# ServerHardware.net
KiCad netlist of a schematic drawn in EAGLE
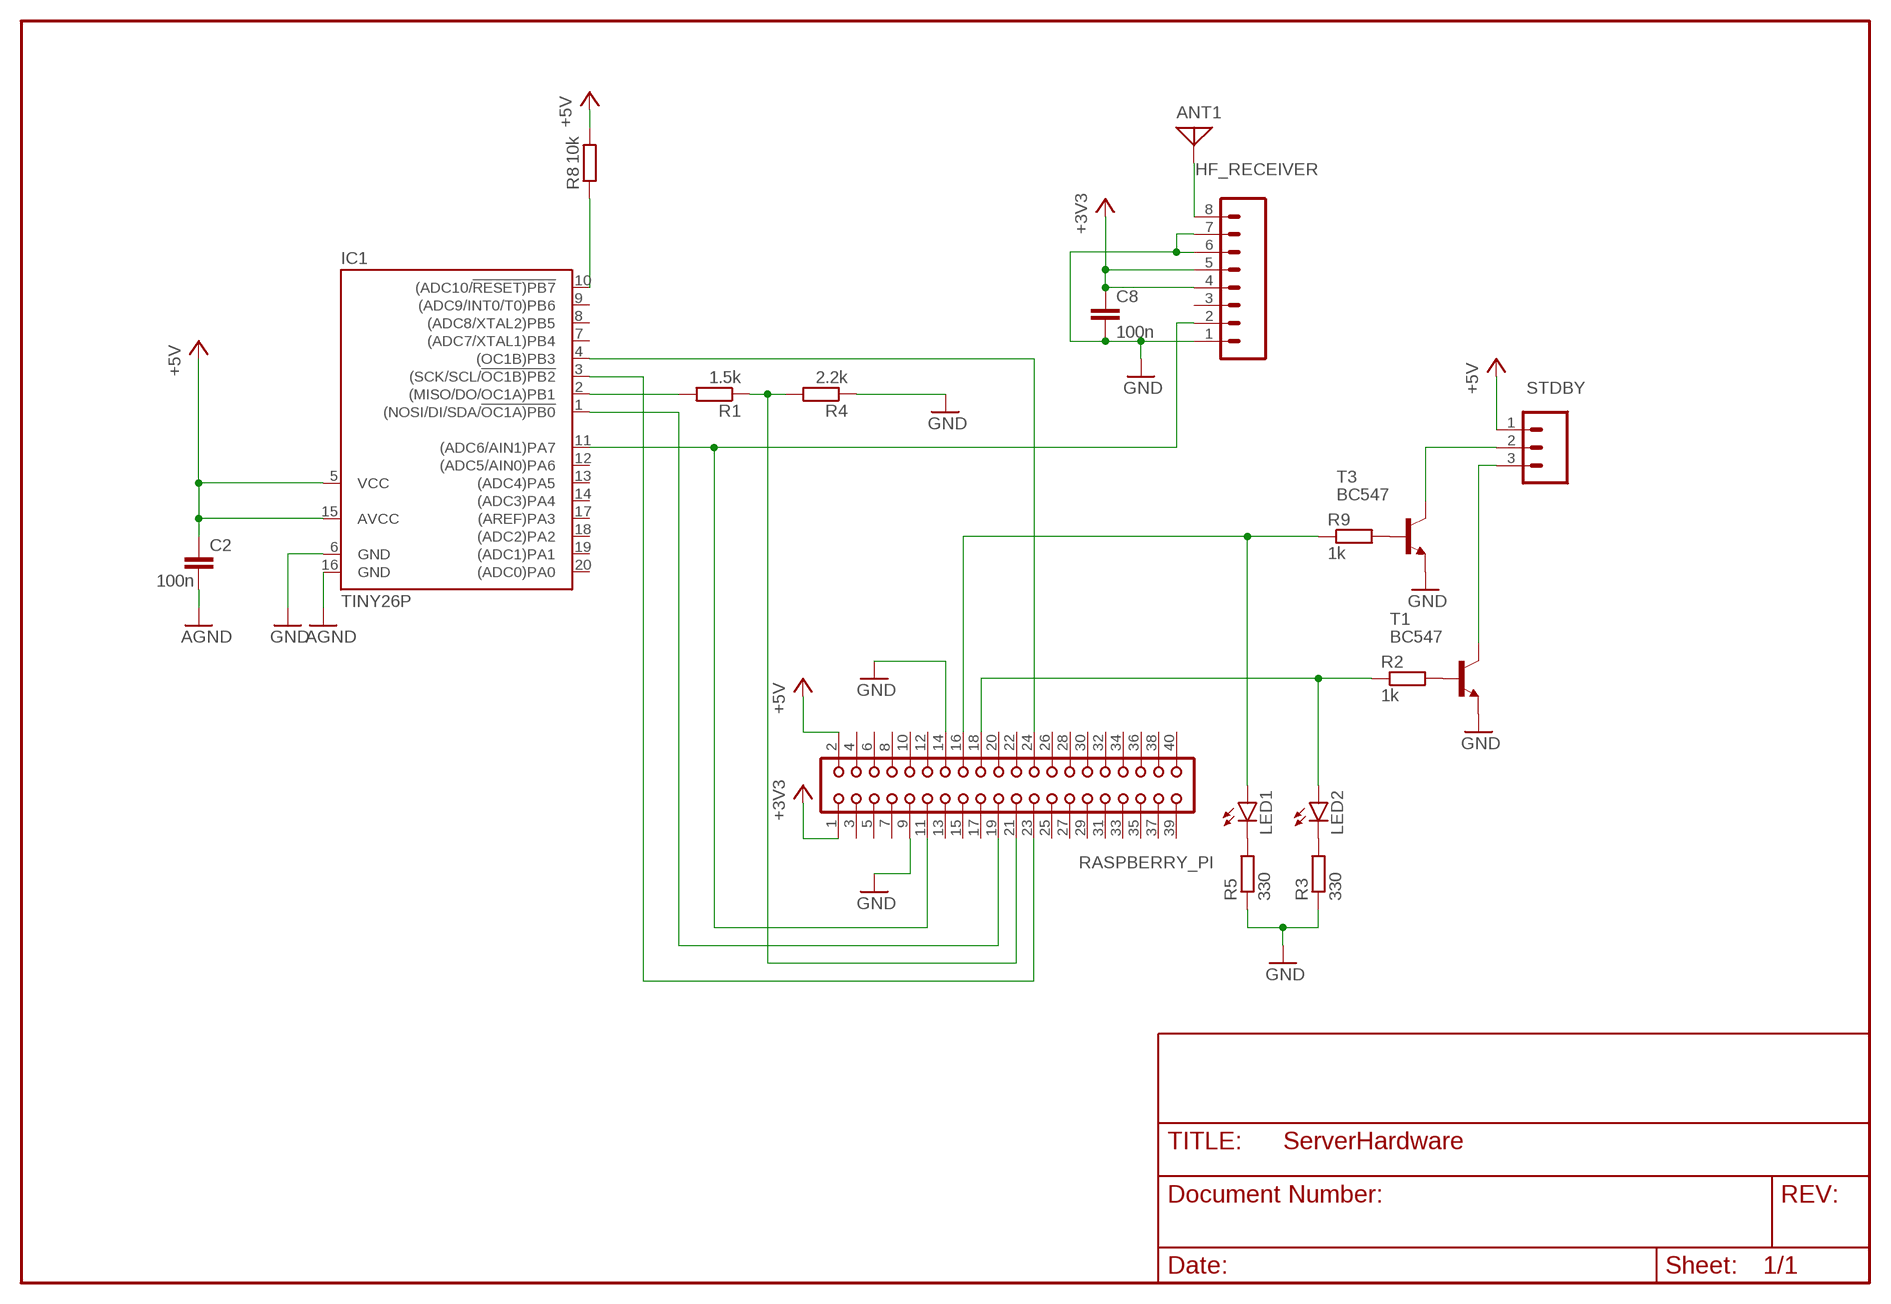
[diagram p0: schematic, sheet 1]

(export (version "E")
  (design (tool "Eeschema 10.0.6"))
  (components
    (comp (ref "ANT1")
      (value "ANTENNA")
      (footprint "eagle-import:PAD-01")
      (libsource (lib "eagle-import") (part "ANTENNA"))
    )
    (comp (ref "C2")
      (value "100n")
      (footprint "eagle-import:C025-024X044")
      (libsource (lib "eagle-import") (part "C-EU025-024X044"))
    )
    (comp (ref "C8")
      (value "100n")
      (footprint "eagle-import:C025-024X044")
      (libsource (lib "eagle-import") (part "C-EU025-024X044"))
    )
    (comp (ref "HF_RECEIVER")
      (value "M08")
      (footprint "eagle-import:08P")
      (libsource (lib "eagle-import") (part "M08"))
    )
    (comp (ref "IC1")
      (value "TINY26P")
      (footprint "eagle-import:DIL20")
      (libsource (lib "eagle-import") (part "TINY26P"))
    )
    (comp (ref "LED1")
      (value "LED5MM")
      (footprint "eagle-import:LED5MM")
      (libsource (lib "eagle-import") (part "LED5MM"))
    )
    (comp (ref "LED2")
      (value "LED5MM")
      (footprint "eagle-import:LED5MM")
      (libsource (lib "eagle-import") (part "LED5MM"))
    )
    (comp (ref "R1")
      (value "1.5k")
      (footprint "eagle-import:0204_5")
      (libsource (lib "eagle-import") (part "R-EU_0204/5"))
    )
    (comp (ref "R2")
      (value "1k")
      (footprint "eagle-import:0204_5")
      (libsource (lib "eagle-import") (part "R-EU_0204/5"))
    )
    (comp (ref "R3")
      (value "330")
      (footprint "eagle-import:0204_5")
      (libsource (lib "eagle-import") (part "R-EU_0204/5"))
    )
    (comp (ref "R4")
      (value "2.2k")
      (footprint "eagle-import:0204_5")
      (libsource (lib "eagle-import") (part "R-EU_0204/5"))
    )
    (comp (ref "R5")
      (value "330")
      (footprint "eagle-import:0204_5")
      (libsource (lib "eagle-import") (part "R-EU_0204/5"))
    )
    (comp (ref "R8")
      (value "10k")
      (footprint "eagle-import:0204_5")
      (libsource (lib "eagle-import") (part "R-EU_0204/5"))
    )
    (comp (ref "R9")
      (value "1k")
      (footprint "eagle-import:0204_5")
      (libsource (lib "eagle-import") (part "R-EU_0204/5"))
    )
    (comp (ref "RASPBERRY_PI")
      (value "CON40")
      (footprint "eagle-import:CON40")
      (libsource (lib "eagle-import") (part "CON40"))
    )
    (comp (ref "STDBY")
      (value "M03")
      (footprint "eagle-import:03P")
      (libsource (lib "eagle-import") (part "M03"))
    )
    (comp (ref "T1")
      (value "BC547")
      (footprint "eagle-import:TO92")
      (libsource (lib "eagle-import") (part "BC547"))
    )
    (comp (ref "T3")
      (value "BC547")
      (footprint "eagle-import:TO92")
      (libsource (lib "eagle-import") (part "BC547"))
    )
  )
  (nets
    (net (code "1") (name "+3V3") (class "Default")
      (node (ref "C8") (pin "1") (pinfunction "1_1") (pintype "passive"))
      (node (ref "HF_RECEIVER") (pin "4") (pinfunction "4_4") (pintype "passive"))
      (node (ref "HF_RECEIVER") (pin "5") (pinfunction "5_5") (pintype "passive"))
      (node (ref "RASPBERRY_PI") (pin "1") (pinfunction "1_1") (pintype "passive"))
    )
    (net (code "2") (name "+5V") (class "Default")
      (node (ref "C2") (pin "1") (pinfunction "1_1") (pintype "passive"))
      (node (ref "IC1") (pin "15") (pinfunction "AVCC_15") (pintype "power_in"))
      (node (ref "IC1") (pin "5") (pinfunction "VCC_5") (pintype "power_in"))
      (node (ref "R8") (pin "2") (pinfunction "2_2") (pintype "passive"))
      (node (ref "RASPBERRY_PI") (pin "2") (pinfunction "2_2") (pintype "passive"))
      (node (ref "STDBY") (pin "1") (pinfunction "1_1") (pintype "passive"))
    )
    (net (code "3") (name "AGND") (class "Default")
      (node (ref "C2") (pin "2") (pinfunction "2_2") (pintype "passive"))
      (node (ref "C8") (pin "2") (pinfunction "2_2") (pintype "passive"))
      (node (ref "HF_RECEIVER") (pin "1") (pinfunction "1_1") (pintype "passive"))
      (node (ref "HF_RECEIVER") (pin "6") (pinfunction "6_6") (pintype "passive"))
      (node (ref "HF_RECEIVER") (pin "7") (pinfunction "7_7") (pintype "passive"))
      (node (ref "IC1") (pin "16") (pinfunction "GND_16") (pintype "power_in"))
      (node (ref "IC1") (pin "6") (pinfunction "GND_6") (pintype "power_in"))
      (node (ref "R3") (pin "1") (pinfunction "1_1") (pintype "passive"))
      (node (ref "R4") (pin "1") (pinfunction "1_1") (pintype "passive"))
      (node (ref "R5") (pin "1") (pinfunction "1_1") (pintype "passive"))
      (node (ref "RASPBERRY_PI") (pin "14") (pinfunction "14_14") (pintype "passive"))
      (node (ref "RASPBERRY_PI") (pin "9") (pinfunction "9_9") (pintype "passive"))
      (node (ref "T1") (pin "1") (pinfunction "E_1") (pintype "passive"))
      (node (ref "T3") (pin "1") (pinfunction "E_1") (pintype "passive"))
    )
    (net (code "4") (name "Net-(ANT1-Pad1)") (class "Default")
      (node (ref "ANT1") (pin "1") (pinfunction "1_1") (pintype "output"))
      (node (ref "HF_RECEIVER") (pin "8") (pinfunction "8_8") (pintype "passive"))
    )
    (net (code "5") (name "Net-(IC1-(ADC6{slash}AIN1)PA7)") (class "Default")
      (node (ref "HF_RECEIVER") (pin "2") (pinfunction "2_2") (pintype "passive"))
      (node (ref "IC1") (pin "11") (pinfunction "(ADC6/AIN1)PA7_11") (pintype "bidirectional"))
      (node (ref "RASPBERRY_PI") (pin "11") (pinfunction "11_11") (pintype "passive"))
    )
    (net (code "6") (name "Net-(IC1-(ADC10{slash}~{RESET})PB7)") (class "Default")
      (node (ref "IC1") (pin "10") (pinfunction "(ADC10/~{RESET})PB7_10") (pintype "bidirectional"))
      (node (ref "R8") (pin "1") (pinfunction "1_1") (pintype "passive"))
    )
    (net (code "7") (name "Net-(IC1-(MISO{slash}DO{slash}OC1A)PB1)") (class "Default")
      (node (ref "IC1") (pin "2") (pinfunction "(MISO/DO/OC1A)PB1_2") (pintype "bidirectional"))
      (node (ref "R1") (pin "2") (pinfunction "2_2") (pintype "passive"))
    )
    (net (code "8") (name "Net-(IC1-(NOSI{slash}DI{slash}SDA{slash}~{OC1A})PB0)") (class "Default")
      (node (ref "IC1") (pin "1") (pinfunction "(NOSI/DI/SDA/~{OC1A})PB0_1") (pintype "bidirectional"))
      (node (ref "RASPBERRY_PI") (pin "19") (pinfunction "19_19") (pintype "passive"))
    )
    (net (code "9") (name "Net-(IC1-(OC1B)PB3)") (class "Default")
      (node (ref "IC1") (pin "4") (pinfunction "(OC1B)PB3_4") (pintype "bidirectional"))
      (node (ref "RASPBERRY_PI") (pin "24") (pinfunction "24_24") (pintype "passive"))
    )
    (net (code "10") (name "Net-(IC1-(SCK{slash}SCL{slash}~{OC1B})PB2)") (class "Default")
      (node (ref "IC1") (pin "3") (pinfunction "(SCK/SCL/~{OC1B})PB2_3") (pintype "bidirectional"))
      (node (ref "RASPBERRY_PI") (pin "23") (pinfunction "23_23") (pintype "passive"))
    )
    (net (code "11") (name "Net-(LED1-C)") (class "Default")
      (node (ref "LED1") (pin "K") (pinfunction "C_K") (pintype "passive"))
      (node (ref "R5") (pin "2") (pinfunction "2_2") (pintype "passive"))
    )
    (net (code "12") (name "Net-(LED1-PadA)") (class "Default")
      (node (ref "LED1") (pin "A") (pinfunction "A_A") (pintype "passive"))
      (node (ref "R9") (pin "1") (pinfunction "1_1") (pintype "passive"))
      (node (ref "RASPBERRY_PI") (pin "16") (pinfunction "16_16") (pintype "passive"))
    )
    (net (code "13") (name "Net-(LED2-C)") (class "Default")
      (node (ref "LED2") (pin "K") (pinfunction "C_K") (pintype "passive"))
      (node (ref "R3") (pin "2") (pinfunction "2_2") (pintype "passive"))
    )
    (net (code "14") (name "Net-(LED2-PadA)") (class "Default")
      (node (ref "LED2") (pin "A") (pinfunction "A_A") (pintype "passive"))
      (node (ref "R2") (pin "1") (pinfunction "1_1") (pintype "passive"))
      (node (ref "RASPBERRY_PI") (pin "18") (pinfunction "18_18") (pintype "passive"))
    )
    (net (code "15") (name "Net-(R1-Pad1)") (class "Default")
      (node (ref "R1") (pin "1") (pinfunction "1_1") (pintype "passive"))
      (node (ref "R4") (pin "2") (pinfunction "2_2") (pintype "passive"))
      (node (ref "RASPBERRY_PI") (pin "21") (pinfunction "21_21") (pintype "passive"))
    )
    (net (code "16") (name "Net-(T1-B)") (class "Default")
      (node (ref "R2") (pin "2") (pinfunction "2_2") (pintype "passive"))
      (node (ref "T1") (pin "2") (pinfunction "B_2") (pintype "passive"))
    )
    (net (code "17") (name "Net-(T1-C)") (class "Default")
      (node (ref "STDBY") (pin "3") (pinfunction "3_3") (pintype "passive"))
      (node (ref "T1") (pin "3") (pinfunction "C_3") (pintype "passive"))
    )
    (net (code "18") (name "Net-(T3-B)") (class "Default")
      (node (ref "R9") (pin "2") (pinfunction "2_2") (pintype "passive"))
      (node (ref "T3") (pin "2") (pinfunction "B_2") (pintype "passive"))
    )
    (net (code "19") (name "Net-(T3-C)") (class "Default")
      (node (ref "STDBY") (pin "2") (pinfunction "2_2") (pintype "passive"))
      (node (ref "T3") (pin "3") (pinfunction "C_3") (pintype "passive"))
    )
    (net (code "20") (name "unconnected-(HF_RECEIVER-Pad3)") (class "Default")
      (node (ref "HF_RECEIVER") (pin "3") (pinfunction "3_3") (pintype "passive"))
    )
    (net (code "21") (name "unconnected-(IC1-(ADC0)PA0-Pad20)") (class "Default")
      (node (ref "IC1") (pin "20") (pinfunction "(ADC0)PA0_20") (pintype "bidirectional"))
    )
    (net (code "22") (name "unconnected-(IC1-(ADC1)PA1-Pad19)") (class "Default")
      (node (ref "IC1") (pin "19") (pinfunction "(ADC1)PA1_19") (pintype "bidirectional"))
    )
    (net (code "23") (name "unconnected-(IC1-(ADC2)PA2-Pad18)") (class "Default")
      (node (ref "IC1") (pin "18") (pinfunction "(ADC2)PA2_18") (pintype "bidirectional"))
    )
    (net (code "24") (name "unconnected-(IC1-(ADC3)PA4-Pad14)") (class "Default")
      (node (ref "IC1") (pin "14") (pinfunction "(ADC3)PA4_14") (pintype "bidirectional"))
    )
    (net (code "25") (name "unconnected-(IC1-(ADC4)PA5-Pad13)") (class "Default")
      (node (ref "IC1") (pin "13") (pinfunction "(ADC4)PA5_13") (pintype "bidirectional"))
    )
    (net (code "26") (name "unconnected-(IC1-(ADC5{slash}AIN0)PA6-Pad12)") (class "Default")
      (node (ref "IC1") (pin "12") (pinfunction "(ADC5/AIN0)PA6_12") (pintype "bidirectional"))
    )
    (net (code "27") (name "unconnected-(IC1-(ADC7{slash}XTAL1)PB4-Pad7)") (class "Default")
      (node (ref "IC1") (pin "7") (pinfunction "(ADC7/XTAL1)PB4_7") (pintype "bidirectional"))
    )
    (net (code "28") (name "unconnected-(IC1-(ADC8{slash}XTAL2)PB5-Pad8)") (class "Default")
      (node (ref "IC1") (pin "8") (pinfunction "(ADC8/XTAL2)PB5_8") (pintype "bidirectional"))
    )
    (net (code "29") (name "unconnected-(IC1-(ADC9{slash}INT0{slash}T0)PB6-Pad9)") (class "Default")
      (node (ref "IC1") (pin "9") (pinfunction "(ADC9/INT0/T0)PB6_9") (pintype "bidirectional"))
    )
    (net (code "30") (name "unconnected-(IC1-(AREF)PA3-Pad17)") (class "Default")
      (node (ref "IC1") (pin "17") (pinfunction "(AREF)PA3_17") (pintype "bidirectional"))
    )
    (net (code "31") (name "unconnected-(RASPBERRY_PI-Pad3)") (class "Default")
      (node (ref "RASPBERRY_PI") (pin "3") (pinfunction "3_3") (pintype "passive"))
    )
    (net (code "32") (name "unconnected-(RASPBERRY_PI-Pad4)") (class "Default")
      (node (ref "RASPBERRY_PI") (pin "4") (pinfunction "4_4") (pintype "passive"))
    )
    (net (code "33") (name "unconnected-(RASPBERRY_PI-Pad5)") (class "Default")
      (node (ref "RASPBERRY_PI") (pin "5") (pinfunction "5_5") (pintype "passive"))
    )
    (net (code "34") (name "unconnected-(RASPBERRY_PI-Pad6)") (class "Default")
      (node (ref "RASPBERRY_PI") (pin "6") (pinfunction "6_6") (pintype "passive"))
    )
    (net (code "35") (name "unconnected-(RASPBERRY_PI-Pad7)") (class "Default")
      (node (ref "RASPBERRY_PI") (pin "7") (pinfunction "7_7") (pintype "passive"))
    )
    (net (code "36") (name "unconnected-(RASPBERRY_PI-Pad8)") (class "Default")
      (node (ref "RASPBERRY_PI") (pin "8") (pinfunction "8_8") (pintype "passive"))
    )
    (net (code "37") (name "unconnected-(RASPBERRY_PI-Pad10)") (class "Default")
      (node (ref "RASPBERRY_PI") (pin "10") (pinfunction "10_10") (pintype "passive"))
    )
    (net (code "38") (name "unconnected-(RASPBERRY_PI-Pad12)") (class "Default")
      (node (ref "RASPBERRY_PI") (pin "12") (pinfunction "12_12") (pintype "passive"))
    )
    (net (code "39") (name "unconnected-(RASPBERRY_PI-Pad13)") (class "Default")
      (node (ref "RASPBERRY_PI") (pin "13") (pinfunction "13_13") (pintype "passive"))
    )
    (net (code "40") (name "unconnected-(RASPBERRY_PI-Pad15)") (class "Default")
      (node (ref "RASPBERRY_PI") (pin "15") (pinfunction "15_15") (pintype "passive"))
    )
    (net (code "41") (name "unconnected-(RASPBERRY_PI-Pad17)") (class "Default")
      (node (ref "RASPBERRY_PI") (pin "17") (pinfunction "17_17") (pintype "passive"))
    )
    (net (code "42") (name "unconnected-(RASPBERRY_PI-Pad20)") (class "Default")
      (node (ref "RASPBERRY_PI") (pin "20") (pinfunction "20_20") (pintype "passive"))
    )
    (net (code "43") (name "unconnected-(RASPBERRY_PI-Pad22)") (class "Default")
      (node (ref "RASPBERRY_PI") (pin "22") (pinfunction "22_22") (pintype "passive"))
    )
    (net (code "44") (name "unconnected-(RASPBERRY_PI-Pad25)") (class "Default")
      (node (ref "RASPBERRY_PI") (pin "25") (pinfunction "25_25") (pintype "passive"))
    )
    (net (code "45") (name "unconnected-(RASPBERRY_PI-Pad26)") (class "Default")
      (node (ref "RASPBERRY_PI") (pin "26") (pinfunction "26_26") (pintype "passive"))
    )
    (net (code "46") (name "unconnected-(RASPBERRY_PI-Pad27)") (class "Default")
      (node (ref "RASPBERRY_PI") (pin "27") (pinfunction "27_27") (pintype "passive"))
    )
    (net (code "47") (name "unconnected-(RASPBERRY_PI-Pad28)") (class "Default")
      (node (ref "RASPBERRY_PI") (pin "28") (pinfunction "28_28") (pintype "passive"))
    )
    (net (code "48") (name "unconnected-(RASPBERRY_PI-Pad29)") (class "Default")
      (node (ref "RASPBERRY_PI") (pin "29") (pinfunction "29_29") (pintype "passive"))
    )
    (net (code "49") (name "unconnected-(RASPBERRY_PI-Pad30)") (class "Default")
      (node (ref "RASPBERRY_PI") (pin "30") (pinfunction "30_30") (pintype "passive"))
    )
    (net (code "50") (name "unconnected-(RASPBERRY_PI-Pad31)") (class "Default")
      (node (ref "RASPBERRY_PI") (pin "31") (pinfunction "31_31") (pintype "passive"))
    )
    (net (code "51") (name "unconnected-(RASPBERRY_PI-Pad32)") (class "Default")
      (node (ref "RASPBERRY_PI") (pin "32") (pinfunction "32_32") (pintype "passive"))
    )
    (net (code "52") (name "unconnected-(RASPBERRY_PI-Pad33)") (class "Default")
      (node (ref "RASPBERRY_PI") (pin "33") (pinfunction "33_33") (pintype "passive"))
    )
    (net (code "53") (name "unconnected-(RASPBERRY_PI-Pad34)") (class "Default")
      (node (ref "RASPBERRY_PI") (pin "34") (pinfunction "34_34") (pintype "passive"))
    )
    (net (code "54") (name "unconnected-(RASPBERRY_PI-Pad35)") (class "Default")
      (node (ref "RASPBERRY_PI") (pin "35") (pinfunction "35_35") (pintype "passive"))
    )
    (net (code "55") (name "unconnected-(RASPBERRY_PI-Pad36)") (class "Default")
      (node (ref "RASPBERRY_PI") (pin "36") (pinfunction "36_36") (pintype "passive"))
    )
    (net (code "56") (name "unconnected-(RASPBERRY_PI-Pad37)") (class "Default")
      (node (ref "RASPBERRY_PI") (pin "37") (pinfunction "37_37") (pintype "passive"))
    )
    (net (code "57") (name "unconnected-(RASPBERRY_PI-Pad38)") (class "Default")
      (node (ref "RASPBERRY_PI") (pin "38") (pinfunction "38_38") (pintype "passive"))
    )
    (net (code "58") (name "unconnected-(RASPBERRY_PI-Pad39)") (class "Default")
      (node (ref "RASPBERRY_PI") (pin "39") (pinfunction "39_39") (pintype "passive"))
    )
    (net (code "59") (name "unconnected-(RASPBERRY_PI-Pad40)") (class "Default")
      (node (ref "RASPBERRY_PI") (pin "40") (pinfunction "40_40") (pintype "passive"))
    )
  )
)
